# target.net
KiCad netlist of a schematic drawn in EAGLE
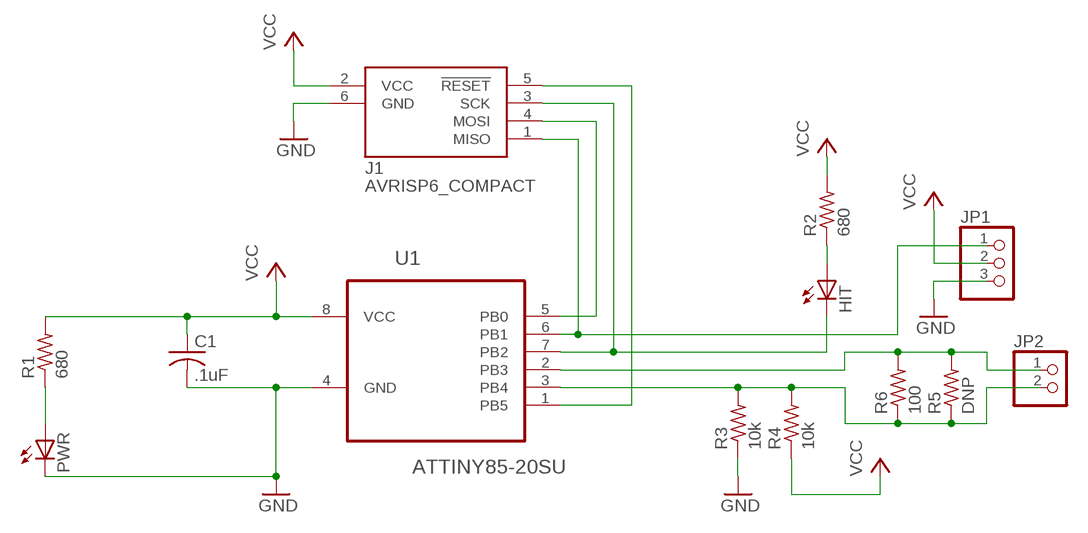
[diagram p0: schematic, sheet 1]

(export (version "E")
  (design (tool "Eeschema 10.0.6"))
  (components
    (comp (ref "C1")
      (value ".1uF")
      (footprint "eagle-import:C0805")
      (libsource (lib "eagle-import") (part "C-USC0805"))
    )
    (comp (ref "HIT")
      (value "LEDSML0805")
      (footprint "eagle-import:SML0805")
      (libsource (lib "eagle-import") (part "LEDSML0805"))
    )
    (comp (ref "J1")
      (value "AVRISP6_COMPACT")
      (footprint "eagle-import:CON6P2R")
      (libsource (lib "eagle-import") (part "AVRISP6_COMPACT"))
    )
    (comp (ref "JP1")
      (value "PINHD-1X3")
      (footprint "eagle-import:1X03")
      (libsource (lib "eagle-import") (part "PINHD-1X3"))
    )
    (comp (ref "JP2")
      (value "PINHD-1X2")
      (footprint "eagle-import:1X02")
      (libsource (lib "eagle-import") (part "PINHD-1X2"))
    )
    (comp (ref "PWR")
      (value "LEDSML0805")
      (footprint "eagle-import:SML0805")
      (libsource (lib "eagle-import") (part "LEDSML0805"))
    )
    (comp (ref "R1")
      (value "680")
      (footprint "eagle-import:R0805")
      (libsource (lib "eagle-import") (part "R-US_R0805"))
    )
    (comp (ref "R2")
      (value "680")
      (footprint "eagle-import:R0805")
      (libsource (lib "eagle-import") (part "R-US_R0805"))
    )
    (comp (ref "R3")
      (value "10k")
      (footprint "eagle-import:R0805")
      (libsource (lib "eagle-import") (part "R-US_R0805"))
    )
    (comp (ref "R4")
      (value "10k")
      (footprint "eagle-import:R0805")
      (libsource (lib "eagle-import") (part "R-US_R0805"))
    )
    (comp (ref "R5")
      (value "DNP")
      (footprint "eagle-import:R0805")
      (libsource (lib "eagle-import") (part "R-US_R0805"))
    )
    (comp (ref "R6")
      (value "100")
      (footprint "eagle-import:R0805")
      (libsource (lib "eagle-import") (part "R-US_R0805"))
    )
    (comp (ref "U1")
      (value "ATTINY85-20SU")
      (footprint "eagle-import:SOIC127P798X216-8N")
      (libsource (lib "eagle-import") (part "ATTINY85-20SU"))
    )
  )
  (nets
    (net (code "1") (name "GND") (class "Default")
      (node (ref "C1") (pin "2") (pinfunction "2_2") (pintype "passive"))
      (node (ref "J1") (pin "6") (pinfunction "GND_6") (pintype "power_in"))
      (node (ref "JP1") (pin "3") (pinfunction "3_3") (pintype "passive"))
      (node (ref "PWR") (pin "C") (pinfunction "C_C") (pintype "passive"))
      (node (ref "R3") (pin "1") (pinfunction "1_1") (pintype "passive"))
      (node (ref "U1") (pin "4") (pinfunction "GND_4") (pintype "passive"))
    )
    (net (code "2") (name "Net-(HIT-PadA)") (class "Default")
      (node (ref "HIT") (pin "A") (pinfunction "A_A") (pintype "passive"))
      (node (ref "R2") (pin "1") (pinfunction "1_1") (pintype "passive"))
    )
    (net (code "3") (name "Net-(J1-MISO)") (class "Default")
      (node (ref "J1") (pin "1") (pinfunction "MISO_1") (pintype "input"))
      (node (ref "JP1") (pin "1") (pinfunction "1_1") (pintype "passive"))
      (node (ref "U1") (pin "6") (pinfunction "PB1_6") (pintype "bidirectional"))
    )
    (net (code "4") (name "Net-(J1-MOSI)") (class "Default")
      (node (ref "J1") (pin "4") (pinfunction "MOSI_4") (pintype "output"))
      (node (ref "U1") (pin "5") (pinfunction "PB0_5") (pintype "bidirectional"))
    )
    (net (code "5") (name "Net-(J1-SCK)") (class "Default")
      (node (ref "HIT") (pin "C") (pinfunction "C_C") (pintype "passive"))
      (node (ref "J1") (pin "3") (pinfunction "SCK_3") (pintype "output"))
      (node (ref "U1") (pin "7") (pinfunction "PB2_7") (pintype "bidirectional"))
    )
    (net (code "6") (name "Net-(J1-~{RESET})") (class "Default")
      (node (ref "J1") (pin "5") (pinfunction "~{RESET}_5") (pintype "output"))
      (node (ref "U1") (pin "1") (pinfunction "PB5_1") (pintype "bidirectional"))
    )
    (net (code "7") (name "Net-(PWR-PadA)") (class "Default")
      (node (ref "PWR") (pin "A") (pinfunction "A_A") (pintype "passive"))
      (node (ref "R1") (pin "1") (pinfunction "1_1") (pintype "passive"))
    )
    (net (code "8") (name "Net-(U1-PB3)") (class "Default")
      (node (ref "JP2") (pin "1") (pinfunction "1_1") (pintype "passive"))
      (node (ref "R5") (pin "2") (pinfunction "2_2") (pintype "passive"))
      (node (ref "R6") (pin "2") (pinfunction "2_2") (pintype "passive"))
      (node (ref "U1") (pin "2") (pinfunction "PB3_2") (pintype "bidirectional"))
    )
    (net (code "9") (name "Net-(U1-PB4)") (class "Default")
      (node (ref "JP2") (pin "2") (pinfunction "2_2") (pintype "passive"))
      (node (ref "R3") (pin "2") (pinfunction "2_2") (pintype "passive"))
      (node (ref "R4") (pin "2") (pinfunction "2_2") (pintype "passive"))
      (node (ref "R5") (pin "1") (pinfunction "1_1") (pintype "passive"))
      (node (ref "R6") (pin "1") (pinfunction "1_1") (pintype "passive"))
      (node (ref "U1") (pin "3") (pinfunction "PB4_3") (pintype "bidirectional"))
    )
    (net (code "10") (name "VCC") (class "Default")
      (node (ref "C1") (pin "1") (pinfunction "1_1") (pintype "passive"))
      (node (ref "J1") (pin "2") (pinfunction "VCC_2") (pintype "power_in"))
      (node (ref "JP1") (pin "2") (pinfunction "2_2") (pintype "passive"))
      (node (ref "R1") (pin "2") (pinfunction "2_2") (pintype "passive"))
      (node (ref "R2") (pin "2") (pinfunction "2_2") (pintype "passive"))
      (node (ref "R4") (pin "1") (pinfunction "1_1") (pintype "passive"))
      (node (ref "U1") (pin "8") (pinfunction "VCC_8") (pintype "power_in"))
    )
  )
)
